# LDO.net
KiCad netlist of a schematic drawn in Altium Designer
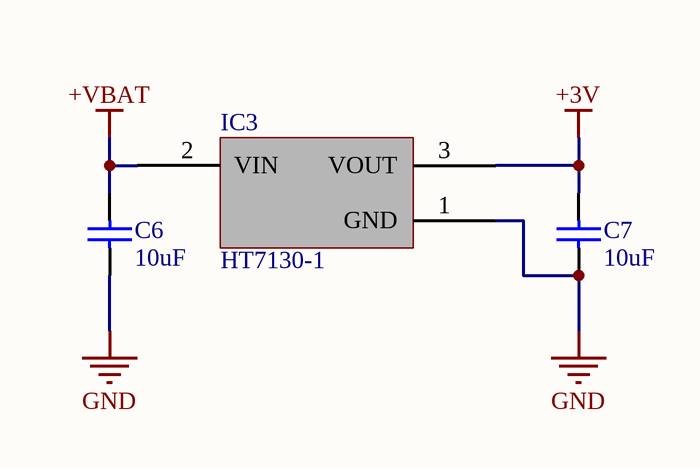
[diagram p0: LDO.SchDoc]

(export (version "E")
  (design (tool "Eeschema 10.0.6"))
  (components
    (comp (ref "C6")
      (value "10uF")
      (footprint "Wurth 0603 capacitor")
      (fields (field (name "Comment") "Generic Capacitor 10uF 0603"))
      (libsource (lib "Passives") (part "Generic Capacitor 10uF 0603"))
    )
    (comp (ref "C7")
      (value "10uF")
      (footprint "Wurth 0603 capacitor")
      (fields (field (name "Comment") "Generic Capacitor 10uF 0603"))
      (libsource (lib "Passives") (part "Generic Capacitor 10uF 0603"))
    )
    (comp (ref "IC3")
      (value "HT7130-1")
      (footprint "UMW SOT89-3")
      (fields
        (field (name "MANUFACTURER") "Holtek")
        (field (name "MANUFACTURER PART NUMBER") "HT7130-1-SOT89TRLF")
      )
      (libsource (lib "LDO") (part "UMW HT7130-1"))
    )
  )
  (nets
    (net (code "1") (name "+3V") (class "Default")
      (node (ref "C7") (pin "2") (pinfunction "2_2") (pintype "passive"))
      (node (ref "IC3") (pin "3") (pinfunction "VOUT_3") (pintype "passive"))
    )
    (net (code "2") (name "+VBAT") (class "Default")
      (node (ref "C6") (pin "2") (pinfunction "2_2") (pintype "passive"))
      (node (ref "IC3") (pin "2") (pinfunction "VIN_2") (pintype "passive"))
    )
    (net (code "3") (name "GND") (class "Default")
      (node (ref "C6") (pin "1") (pinfunction "1_1") (pintype "passive"))
      (node (ref "C7") (pin "1") (pinfunction "1_1") (pintype "passive"))
      (node (ref "IC3") (pin "1") (pinfunction "GND_1") (pintype "passive"))
    )
  )
)
